# SquidPage.net
KiCad netlist of a schematic drawn in Altium Designer
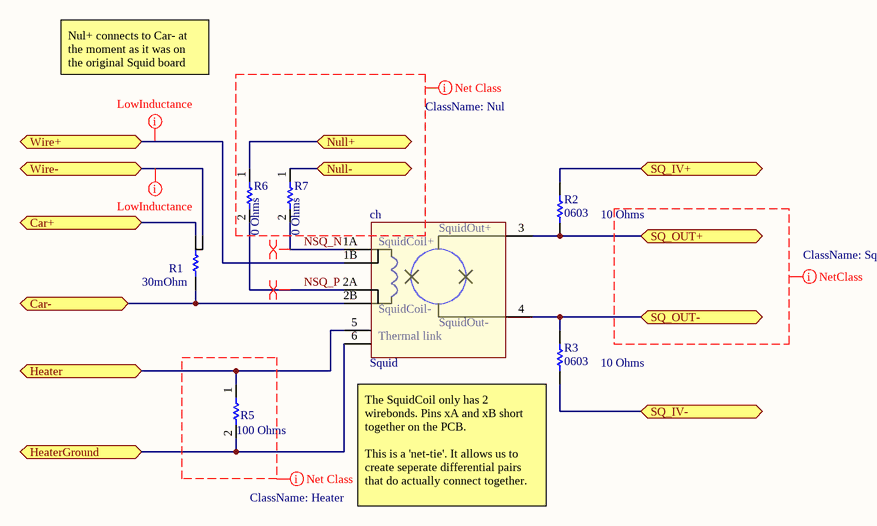
[diagram p0: SquidPage.SchDoc]

(export (version "E")
  (design (tool "Eeschema 10.0.6"))
  (components
    (comp (ref "ch") (value "Squid") (footprint "Squid") (libsource (lib "SPT3G_LCBoard") (part "Squid")))
    (comp (ref "R1")
      (value "30mOhm")
      (footprint "0805NetTie")
      (description "Resistor")
      (fields (field (name "Comment") "ResBias"))
      (libsource (lib "SPT3G_LCBoard") (part "ResBias"))
    )
    (comp (ref "R2")
      (value "0603")
      (footprint "0603")
      (description "RES 1 OHM 1/10W 1% 0603 SMD")
      (fields (field (name "ALTIUM_VALUE") "10 Ohms"))
      (libsource (lib "SPT3G_LCBoard") (part "Res0603"))
    )
    (comp (ref "R3")
      (value "0603")
      (footprint "0603")
      (description "RES 1 OHM 1/10W 1% 0603 SMD")
      (fields (field (name "ALTIUM_VALUE") "10 Ohms"))
      (libsource (lib "SPT3G_LCBoard") (part "Res0603"))
    )
    (comp (ref "R5")
      (value "100 Ohms")
      (footprint "0603-NoSilk")
      (description "Resistor")
      (fields (field (name "Comment") "ResSquidBoard"))
      (libsource (lib "SPT3G_LCBoard") (part "ResSquidBoard"))
    )
    (comp (ref "R6")
      (value "0 Ohms")
      (footprint "0603")
      (description "Resistor")
      (fields (field (name "Comment") "ResSquidBoard"))
      (libsource (lib "SPT3G_LCBoard") (part "ResSquidBoard"))
    )
    (comp (ref "R7")
      (value "0 Ohms")
      (footprint "0603")
      (description "Resistor")
      (fields (field (name "Comment") "ResSquidBoard"))
      (libsource (lib "SPT3G_LCBoard") (part "ResSquidBoard"))
    )
  )
  (nets
    (net (code "1") (name "/Car+") (class "Default")
      (node (ref "R1") (pin "2A") (pinfunction "2_2A") (pintype "passive"))
    )
    (net (code "2") (name "/Car-") (class "Default")
      (node (ref "R1") (pin "1") (pinfunction "1_1") (pintype "passive"))
      (node (ref "ch") (pin "2B") (pinfunction "SquidCoil-_2B") (pintype "passive"))
    )
    (net (code "3") (name "/Heater") (class "Default")
      (node (ref "R5") (pin "1") (pinfunction "1_1") (pintype "passive"))
      (node (ref "ch") (pin "5") (pinfunction "Heater_5") (pintype "passive"))
    )
    (net (code "4") (name "/HeaterGround") (class "Default")
      (node (ref "R5") (pin "2") (pinfunction "2_2") (pintype "passive"))
      (node (ref "ch") (pin "6") (pinfunction "HeaterGnd_6") (pintype "passive"))
    )
    (net (code "5") (name "/NSQ_N") (class "Default")
      (node (ref "R7") (pin "2") (pinfunction "2_2") (pintype "passive"))
      (node (ref "ch") (pin "1A") (pinfunction "SquidCoil+_1A") (pintype "passive"))
    )
    (net (code "6") (name "/NSQ_P") (class "Default")
      (node (ref "R6") (pin "2") (pinfunction "2_2") (pintype "passive"))
      (node (ref "ch") (pin "2A") (pinfunction "SquidCoil-_2A") (pintype "passive"))
    )
    (net (code "7") (name "/Null+") (class "Default")
      (node (ref "R6") (pin "1") (pinfunction "1_1") (pintype "passive"))
    )
    (net (code "8") (name "/Null-") (class "Default")
      (node (ref "R7") (pin "1") (pinfunction "1_1") (pintype "passive"))
    )
    (net (code "9") (name "/SQ_IV+") (class "Default")
      (node (ref "R2") (pin "2") (pinfunction "2_2") (pintype "passive"))
    )
    (net (code "10") (name "/SQ_IV-") (class "Default")
      (node (ref "R3") (pin "1") (pinfunction "1_1") (pintype "passive"))
    )
    (net (code "11") (name "/SQ_OUT+") (class "Default")
      (node (ref "R2") (pin "1") (pinfunction "1_1") (pintype "passive"))
      (node (ref "ch") (pin "3") (pinfunction "SQUID+_3") (pintype "passive"))
    )
    (net (code "12") (name "/SQ_OUT-") (class "Default")
      (node (ref "R3") (pin "2") (pinfunction "2_2") (pintype "passive"))
      (node (ref "ch") (pin "4") (pinfunction "SQUID-_4") (pintype "passive"))
    )
    (net (code "13") (name "/Wire+") (class "Default")
      (node (ref "ch") (pin "1B") (pinfunction "SquidCoil+_1B") (pintype "passive"))
    )
    (net (code "14") (name "/Wire-") (class "Default")
      (node (ref "R1") (pin "2B") (pinfunction "2_2B") (pintype "passive"))
    )
  )
)
